# DenScript_Potentiometer_V1_0.net
KiCad netlist of a schematic drawn in EAGLE
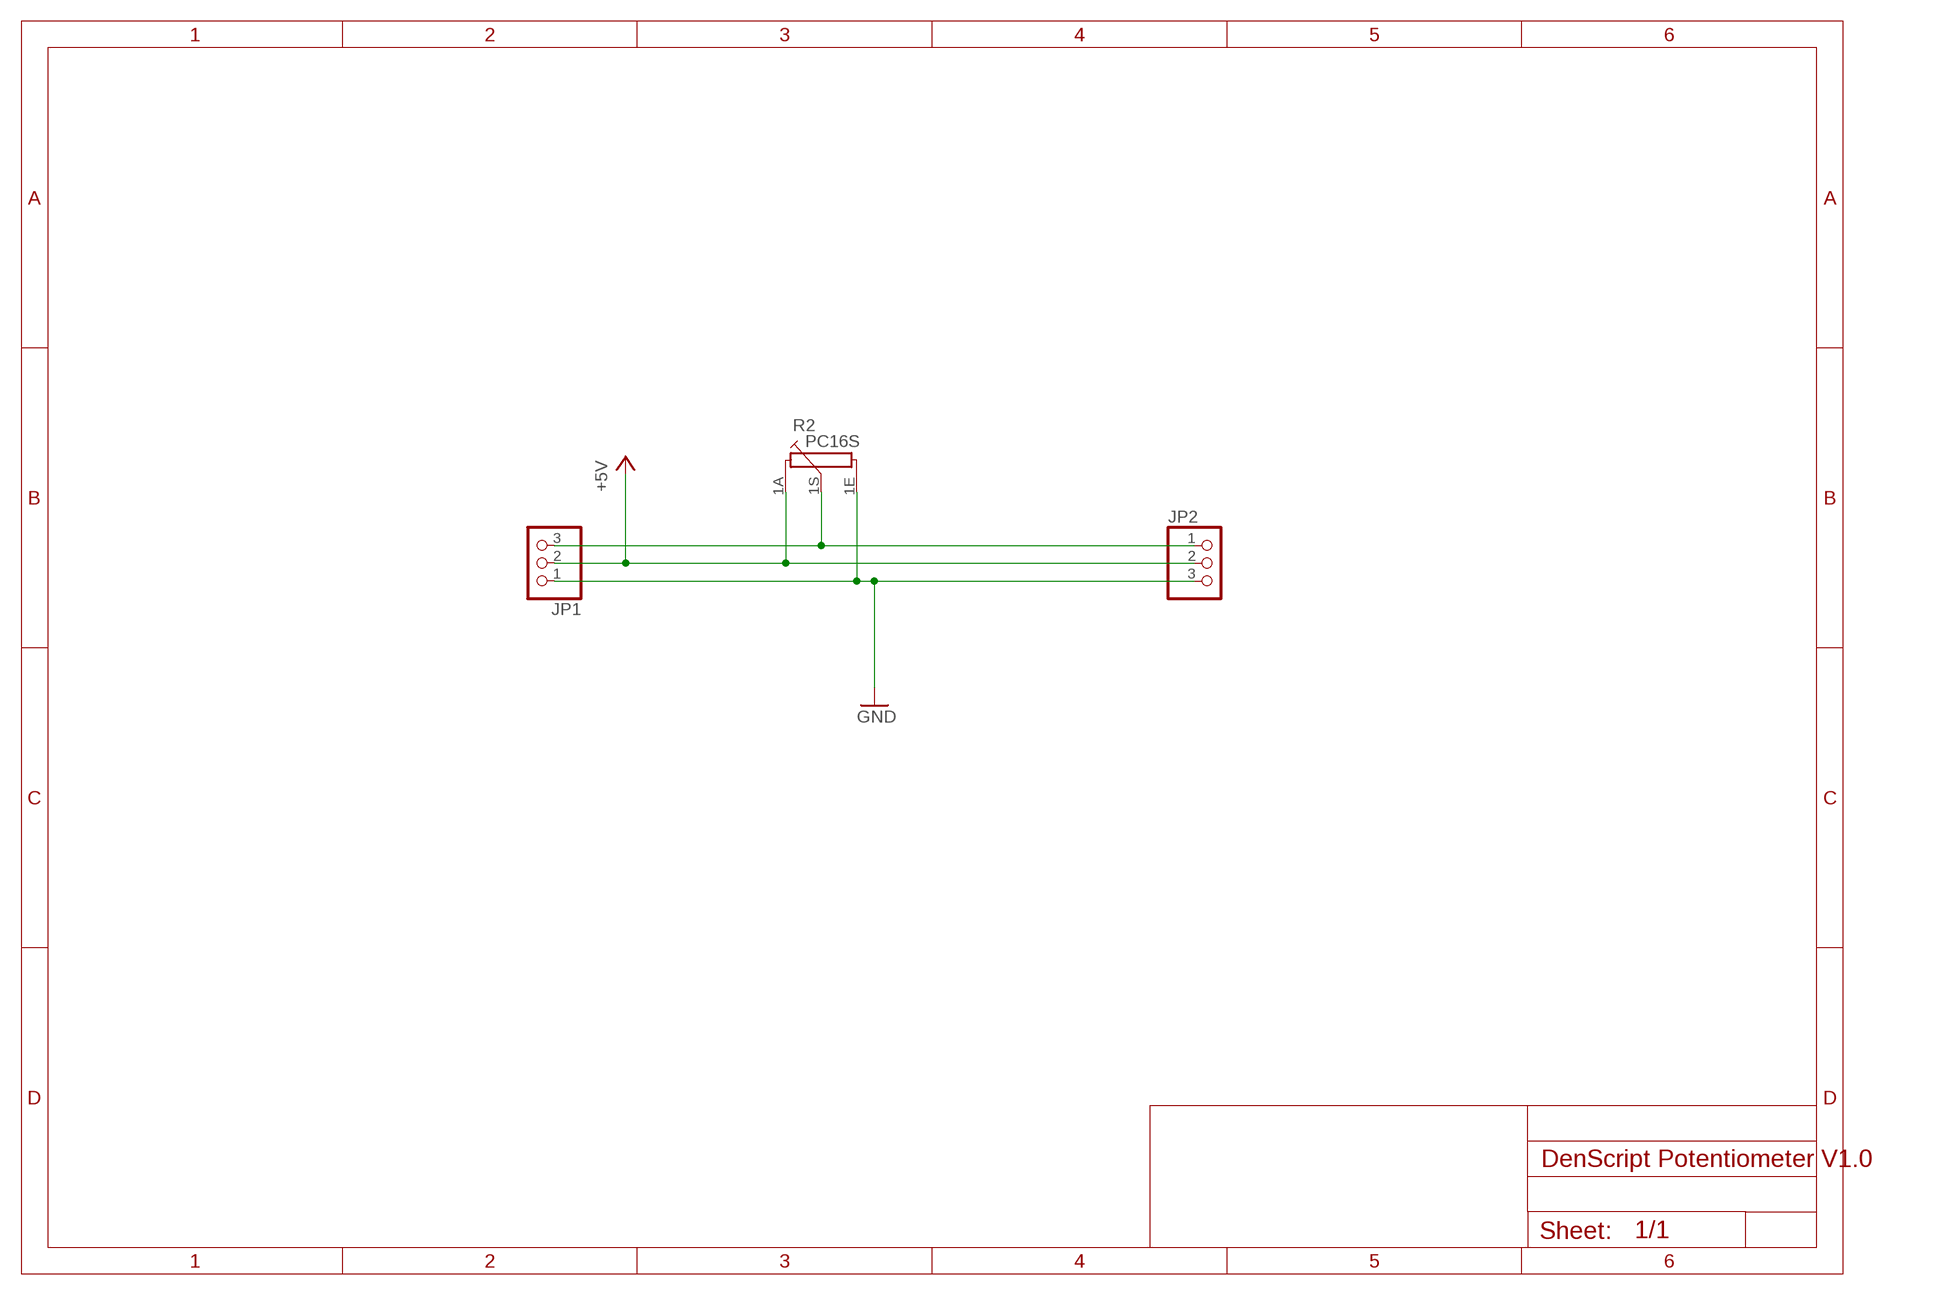
[diagram p0: schematic, sheet 1]

(export (version "E")
  (design (tool "Eeschema 10.0.6"))
  (components
    (comp (ref "JP1")
      (value "PINHD-1X3")
      (footprint "eagle-import:1X03")
      (libsource (lib "eagle-import") (part "PINHD-1X3"))
    )
    (comp (ref "JP2")
      (value "PINHD-1X3")
      (footprint "eagle-import:1X03")
      (libsource (lib "eagle-import") (part "PINHD-1X3"))
    )
    (comp (ref "R2")
      (value "PC16S")
      (footprint "eagle-import:PC16S")
      (libsource (lib "eagle-import") (part "PC16S"))
    )
  )
  (nets
    (net (code "1") (name "+5V") (class "Default")
      (node (ref "JP1") (pin "2") (pinfunction "2_2") (pintype "passive"))
      (node (ref "JP2") (pin "2") (pinfunction "2_2") (pintype "passive"))
      (node (ref "R2") (pin "1A") (pinfunction "1A_1A") (pintype "passive"))
    )
    (net (code "2") (name "GND") (class "Default")
      (node (ref "JP1") (pin "1") (pinfunction "1_1") (pintype "passive"))
      (node (ref "JP2") (pin "3") (pinfunction "3_3") (pintype "passive"))
      (node (ref "R2") (pin "1E") (pinfunction "1E_1E") (pintype "passive"))
    )
    (net (code "3") (name "Net-(JP1-Pad3)") (class "Default")
      (node (ref "JP1") (pin "3") (pinfunction "3_3") (pintype "passive"))
      (node (ref "JP2") (pin "1") (pinfunction "1_1") (pintype "passive"))
      (node (ref "R2") (pin "1S") (pinfunction "1S_1S") (pintype "passive"))
    )
  )
)
